# SCH_BuisnessCard_2024-07-13.net
KiCad netlist of a schematic drawn in EasyEDA
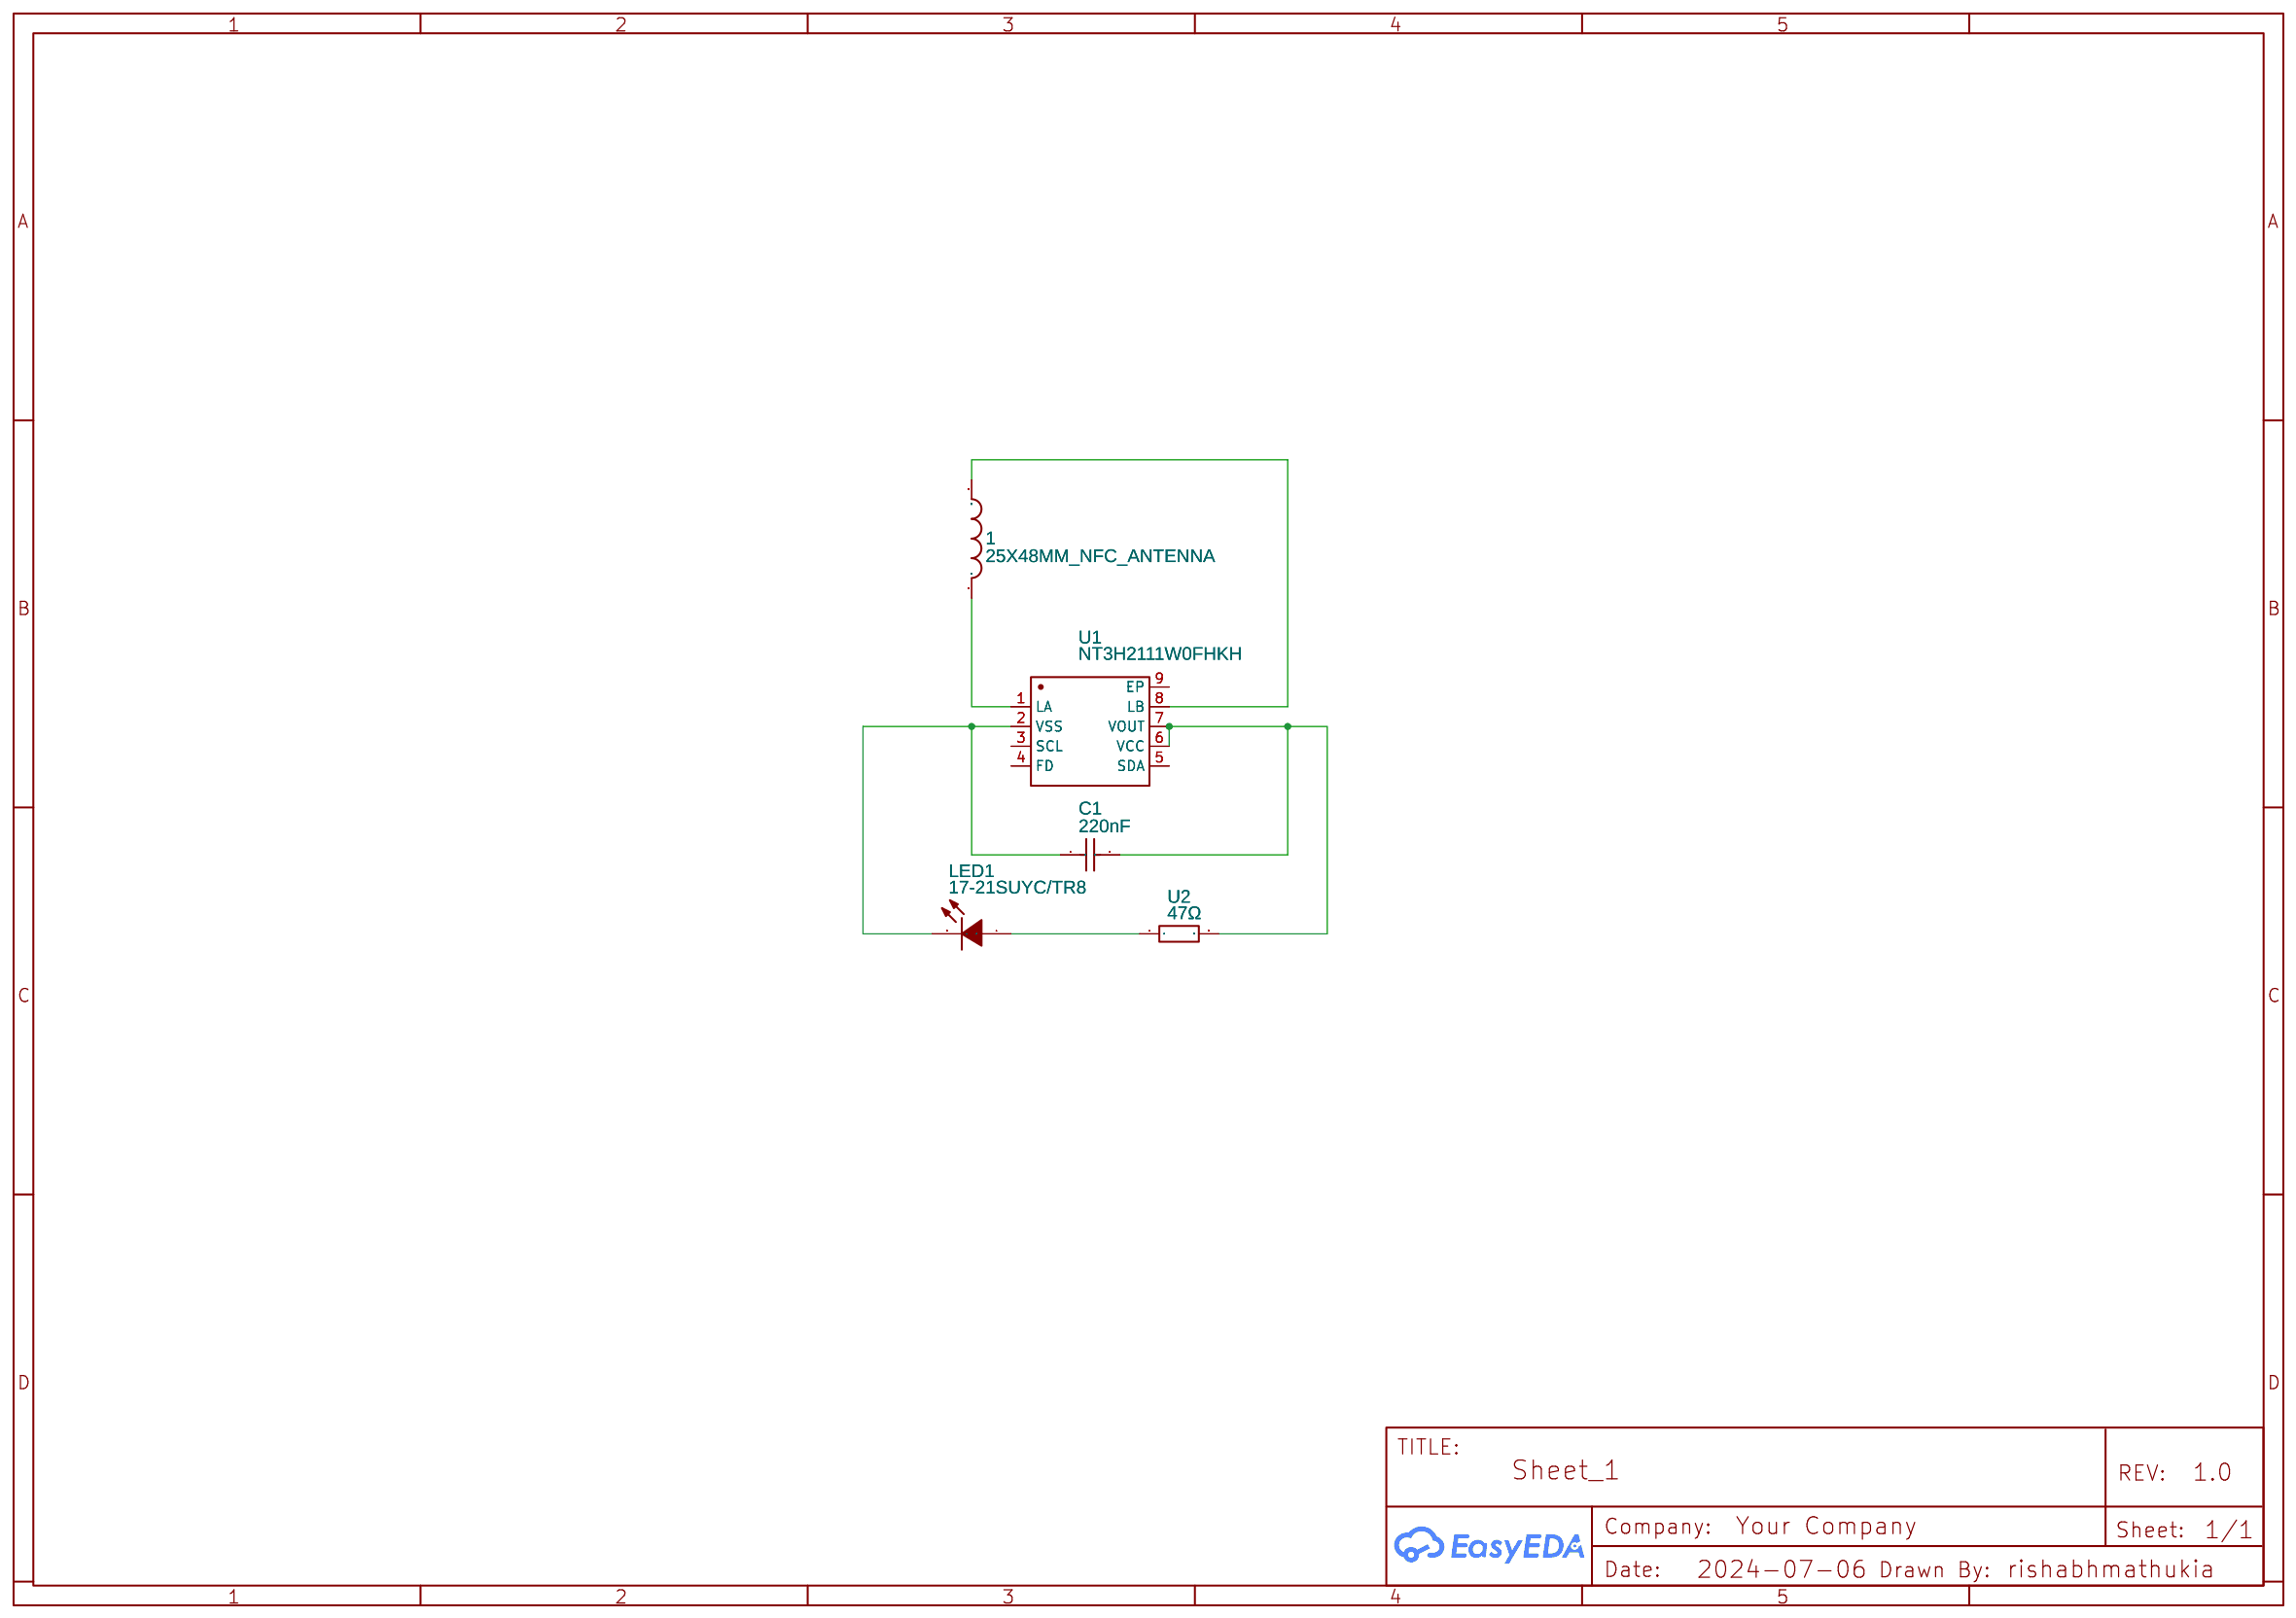
[diagram p0: schematic sheet]

(export (version "E")
  (design (tool "Eeschema 10.0.6"))
  (components
    (comp (ref "1") (value "25X48MM_NFC_ANTENNA") (libsource (lib "") (part "25X48MM_NFC_ANTENNA")))
    (comp (ref "C1")
      (value "220nF")
      (fields (field (name "Manufacturer Part") "C1005X5R0J224KT000F") (field (name "Manufacturer") "TDK"))
      (libsource (lib "") (part "C1005X5R0J224KT000F"))
    )
    (comp (ref "LED1")
      (value "17-21SUYC/TR8")
      (fields (field (name "Manufacturer Part") "KT-0805黄灯") (field (name "Manufacturer") "KENTO"))
      (libsource (lib "") (part "17-21SUYC/TR8"))
    )
    (comp (ref "U1")
      (value "NT3H2111W0FHKH")
      (fields (field (name "Manufacturer") "NXP(恩智浦)"))
      (libsource (lib "") (part "NT3H2111W0FHKH"))
    )
    (comp (ref "U2")
      (value "47Ω")
      (fields (field (name "Manufacturer Part") "MOF3WS-47Ω±5% T") (field (name "Manufacturer") "CCO(千志电子)"))
      (libsource (lib "") (part "MOF3WS-47Ω±5% T"))
    )
  )
  (nets
    (net (code "1") (name "Net-(LED1-+)") (class "Default")
      (node (ref "LED1") (pin "1") (pinfunction "+_1") (pintype "unspecified"))
      (node (ref "U2") (pin "1") (pinfunction "1_1") (pintype "unspecified"))
    )
    (net (code "2") (name "Net-(LED1--)") (class "Default")
      (node (ref "C1") (pin "1") (pinfunction "1_1") (pintype "input"))
      (node (ref "LED1") (pin "2") (pinfunction "-_2") (pintype "unspecified"))
      (node (ref "U1") (pin "2") (pinfunction "VSS_2") (pintype "unspecified"))
    )
    (net (code "3") (name "Net-(U1-LA)") (class "Default")
      (node (ref "1") (pin "P$2") (pinfunction "P$2_P$2") (pintype "bidirectional"))
      (node (ref "U1") (pin "1") (pinfunction "LA_1") (pintype "unspecified"))
    )
    (net (code "4") (name "Net-(U1-LB)") (class "Default")
      (node (ref "1") (pin "P$1") (pinfunction "P$1_P$1") (pintype "bidirectional"))
      (node (ref "U1") (pin "8") (pinfunction "LB_8") (pintype "unspecified"))
    )
    (net (code "5") (name "Net-(U1-VCC)") (class "Default")
      (node (ref "C1") (pin "2") (pinfunction "2_2") (pintype "input"))
      (node (ref "U1") (pin "6") (pinfunction "VCC_6") (pintype "unspecified"))
      (node (ref "U1") (pin "7") (pinfunction "VOUT_7") (pintype "unspecified"))
      (node (ref "U2") (pin "2") (pinfunction "2_2") (pintype "unspecified"))
    )
    (net (code "6") (name "unconnected-(U1-EP-Pad9)") (class "Default")
      (node (ref "U1") (pin "9") (pinfunction "EP_9") (pintype "unspecified"))
    )
    (net (code "7") (name "unconnected-(U1-FD-Pad4)") (class "Default")
      (node (ref "U1") (pin "4") (pinfunction "FD_4") (pintype "unspecified"))
    )
    (net (code "8") (name "unconnected-(U1-SCL-Pad3)") (class "Default")
      (node (ref "U1") (pin "3") (pinfunction "SCL_3") (pintype "unspecified"))
    )
    (net (code "9") (name "unconnected-(U1-SDA-Pad5)") (class "Default")
      (node (ref "U1") (pin "5") (pinfunction "SDA_5") (pintype "unspecified"))
    )
  )
)
